# SCH_New-Project_2024-12-08_14-09-2234_20.net
KiCad netlist of a schematic drawn in EasyEDA
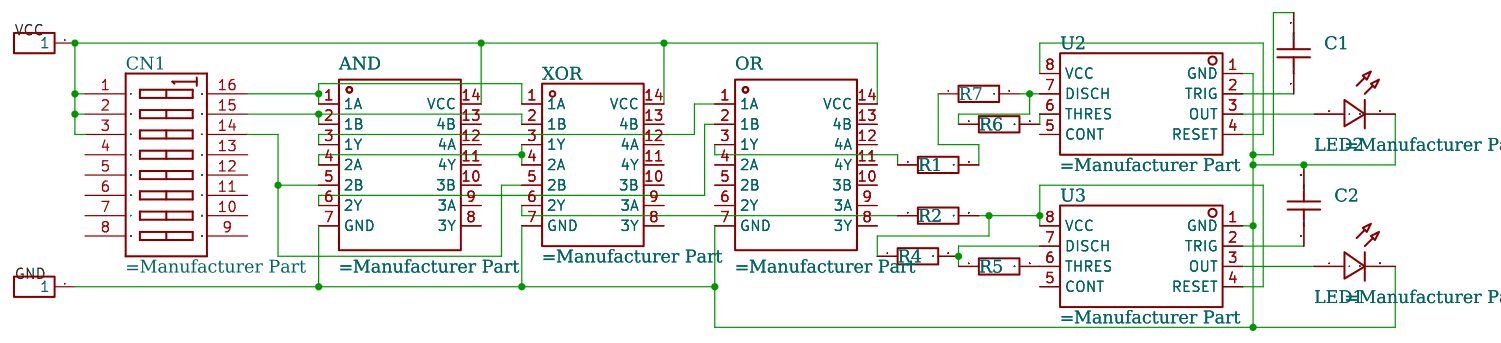
[diagram p0: schematic sheet]

(export (version "E")
  (design (tool "Eeschema 10.0.6"))
  (components
    (comp (ref "AND")
      (value "=Manufacturer Part")
      (fields (field (name "Manufacturer Part") "SN74HC08N") (field (name "Manufacturer") "TI(德州仪器)"))
      (libsource (lib "") (part "Unknown_440_-670"))
    )
    (comp (ref "C1")
      (value "100uF")
      (fields
        (field (name "Manufacturer Part") "50YXJ100MT78X11.5")
        (field (name "Manufacturer") "rubycon(红宝石)")
      )
      (libsource (lib "") (part "Unknown_880_-725"))
    )
    (comp (ref "C2")
      (value "100uF")
      (fields
        (field (name "Manufacturer Part") "50YXJ100MT78X11.5")
        (field (name "Manufacturer") "rubycon(红宝石)")
      )
      (libsource (lib "") (part "Unknown_885_-650"))
    )
    (comp (ref "CN1")
      (value "=Manufacturer Part")
      (fields (field (name "Manufacturer Part") "DS-08RP") (field (name "Manufacturer") "韩国韩荣"))
      (libsource (lib "") (part "Unknown_325_-665"))
    )
    (comp (ref "H1")
      (value "=Manufacturer Part")
      (fields (field (name "Manufacturer Part") "2059-301/998-403") (field (name "Manufacturer") "WAGO(万可)"))
      (libsource (lib "") (part "Unknown_260_-610"))
    )
    (comp (ref "H2")
      (value "=Manufacturer Part")
      (fields (field (name "Manufacturer Part") "2059-301/998-403") (field (name "Manufacturer") "WAGO(万可)"))
      (libsource (lib "") (part "Unknown_260_-730"))
    )
    (comp (ref "LED1")
      (value "=Manufacturer Part")
      (fields (field (name "Manufacturer Part") "LTL-4231N") (field (name "Manufacturer") "LITEON(光宝)"))
      (libsource (lib "") (part "Unknown_910_-620"))
    )
    (comp (ref "LED2")
      (value "=Manufacturer Part")
      (fields (field (name "Manufacturer Part") "LTL-4231N") (field (name "Manufacturer") "LITEON(光宝)"))
      (libsource (lib "") (part "Unknown_910_-695"))
    )
    (comp (ref "OR")
      (value "=Manufacturer Part")
      (fields (field (name "Manufacturer Part") "SN74HC32N") (field (name "Manufacturer") "TI(德州仪器)"))
      (libsource (lib "") (part "Unknown_635_-670"))
    )
    (comp (ref "R1")
      (value "1kΩ")
      (fields (field (name "Manufacturer Part") "RC0402JR-071KL") (field (name "Manufacturer") "YAGEO(国巨)"))
      (libsource (lib "") (part "Unknown_705_-670"))
    )
    (comp (ref "R2")
      (value "1kΩ")
      (fields (field (name "Manufacturer Part") "RC0402JR-071KL") (field (name "Manufacturer") "YAGEO(国巨)"))
      (libsource (lib "") (part "Unknown_705_-645"))
    )
    (comp (ref "R4")
      (value "1kΩ")
      (fields (field (name "Manufacturer Part") "RC0402JR-071KL") (field (name "Manufacturer") "YAGEO(国巨)"))
      (libsource (lib "") (part "Unknown_695_-625"))
    )
    (comp (ref "R5")
      (value "1kΩ")
      (fields (field (name "Manufacturer Part") "RC0402JR-071KL") (field (name "Manufacturer") "YAGEO(国巨)"))
      (libsource (lib "") (part "Unknown_735_-620"))
    )
    (comp (ref "R6")
      (value "1kΩ")
      (fields (field (name "Manufacturer Part") "RC0402JR-071KL") (field (name "Manufacturer") "YAGEO(国巨)"))
      (libsource (lib "") (part "Unknown_735_-690"))
    )
    (comp (ref "R7")
      (value "1kΩ")
      (fields (field (name "Manufacturer Part") "RC0402JR-071KL") (field (name "Manufacturer") "YAGEO(国巨)"))
      (libsource (lib "") (part "Unknown_725_-705"))
    )
    (comp (ref "U2")
      (value "=Manufacturer Part")
      (fields (field (name "Manufacturer Part") "LM555N") (field (name "Manufacturer") "HGSEMI(华冠)"))
      (libsource (lib "") (part "Unknown_805_-700"))
    )
    (comp (ref "U3")
      (value "=Manufacturer Part")
      (fields (field (name "Manufacturer Part") "LM555N") (field (name "Manufacturer") "HGSEMI(华冠)"))
      (libsource (lib "") (part "Unknown_805_-625"))
    )
    (comp (ref "XOR")
      (value "=Manufacturer Part")
      (fields (field (name "Manufacturer Part") "SN74HC86N") (field (name "Manufacturer") "TI(德州仪器)"))
      (libsource (lib "") (part "Unknown_535_-670"))
    )
  )
  (nets
    (net (code "3") (name "Net-(AND-1A)") (class "Default")
      (node (ref "AND") (pin "1") (pinfunction "1A_1") (pintype "unspecified"))
      (node (ref "CN1") (pin "16") (pinfunction "16_16") (pintype "unspecified"))
      (node (ref "XOR") (pin "1") (pinfunction "1A_1") (pintype "unspecified"))
    )
    (net (code "4") (name "Net-(AND-1B)") (class "Default")
      (node (ref "AND") (pin "2") (pinfunction "1B_2") (pintype "unspecified"))
      (node (ref "CN1") (pin "15") (pinfunction "15_15") (pintype "unspecified"))
      (node (ref "XOR") (pin "2") (pinfunction "1B_2") (pintype "unspecified"))
    )
    (net (code "5") (name "Net-(AND-1Y)") (class "Default")
      (node (ref "AND") (pin "3") (pinfunction "1Y_3") (pintype "unspecified"))
      (node (ref "OR") (pin "1") (pinfunction "1A_1") (pintype "unspecified"))
    )
    (net (code "6") (name "Net-(AND-2A)") (class "Default")
      (node (ref "AND") (pin "4") (pinfunction "2A_4") (pintype "unspecified"))
      (node (ref "XOR") (pin "3") (pinfunction "1Y_3") (pintype "unspecified"))
      (node (ref "XOR") (pin "4") (pinfunction "2A_4") (pintype "unspecified"))
    )
    (net (code "7") (name "Net-(AND-2B)") (class "Default")
      (node (ref "AND") (pin "5") (pinfunction "2B_5") (pintype "unspecified"))
      (node (ref "CN1") (pin "14") (pinfunction "14_14") (pintype "unspecified"))
      (node (ref "XOR") (pin "5") (pinfunction "2B_5") (pintype "unspecified"))
    )
    (net (code "8") (name "Net-(AND-2Y)") (class "Default")
      (node (ref "AND") (pin "6") (pinfunction "2Y_6") (pintype "unspecified"))
      (node (ref "OR") (pin "2") (pinfunction "1B_2") (pintype "unspecified"))
    )
    (net (code "9") (name "Net-(AND-GND)") (class "Default")
      (node (ref "AND") (pin "7") (pinfunction "GND_7") (pintype "unspecified"))
      (node (ref "C1") (pin "2") (pinfunction "2_2") (pintype "unspecified"))
      (node (ref "C2") (pin "2") (pinfunction "2_2") (pintype "unspecified"))
      (node (ref "H1") (pin "1") (pinfunction "1_1") (pintype "unspecified"))
      (node (ref "LED1") (pin "2") (pinfunction "C_2") (pintype "unspecified"))
      (node (ref "LED2") (pin "2") (pinfunction "C_2") (pintype "unspecified"))
      (node (ref "OR") (pin "7") (pinfunction "GND_7") (pintype "unspecified"))
      (node (ref "U2") (pin "1") (pinfunction "GND_1") (pintype "unspecified"))
      (node (ref "U3") (pin "1") (pinfunction "GND_1") (pintype "unspecified"))
      (node (ref "XOR") (pin "7") (pinfunction "GND_7") (pintype "unspecified"))
    )
    (net (code "10") (name "Net-(AND-VCC)") (class "Default")
      (node (ref "AND") (pin "14") (pinfunction "VCC_14") (pintype "unspecified"))
      (node (ref "CN1") (pin "1") (pinfunction "A1_1") (pintype "unspecified"))
      (node (ref "CN1") (pin "2") (pinfunction "A2_2") (pintype "unspecified"))
      (node (ref "CN1") (pin "3") (pinfunction "A3_3") (pintype "unspecified"))
      (node (ref "H2") (pin "1") (pinfunction "1_1") (pintype "unspecified"))
      (node (ref "OR") (pin "14") (pinfunction "VCC_14") (pintype "unspecified"))
      (node (ref "XOR") (pin "14") (pinfunction "VCC_14") (pintype "unspecified"))
    )
    (net (code "11") (name "Net-(LED1-A)") (class "Default")
      (node (ref "LED1") (pin "1") (pinfunction "A_1") (pintype "unspecified"))
      (node (ref "U3") (pin "3") (pinfunction "OUT_3") (pintype "unspecified"))
    )
    (net (code "12") (name "Net-(LED2-A)") (class "Default")
      (node (ref "LED2") (pin "1") (pinfunction "A_1") (pintype "unspecified"))
      (node (ref "U2") (pin "3") (pinfunction "OUT_3") (pintype "unspecified"))
    )
    (net (code "13") (name "Net-(OR-1Y)") (class "Default")
      (node (ref "OR") (pin "3") (pinfunction "1Y_3") (pintype "unspecified"))
      (node (ref "R1") (pin "1") (pinfunction "1_1") (pintype "unspecified"))
    )
    (net (code "14") (name "Net-(R1-Pad2)") (class "Default")
      (node (ref "R1") (pin "2") (pinfunction "2_2") (pintype "unspecified"))
      (node (ref "R7") (pin "1") (pinfunction "1_1") (pintype "unspecified"))
    )
    (net (code "15") (name "Net-(U2-DISCH)") (class "Default")
      (node (ref "R6") (pin "1") (pinfunction "1_1") (pintype "unspecified"))
      (node (ref "R7") (pin "2") (pinfunction "2_2") (pintype "unspecified"))
      (node (ref "U2") (pin "7") (pinfunction "DISCH_7") (pintype "unspecified"))
    )
    (net (code "16") (name "Net-(U2-RESET)") (class "Default")
      (node (ref "U2") (pin "4") (pinfunction "RESET_4") (pintype "unspecified"))
      (node (ref "U2") (pin "8") (pinfunction "VCC_8") (pintype "unspecified"))
    )
    (net (code "17") (name "Net-(U2-THRES)") (class "Default")
      (node (ref "R6") (pin "2") (pinfunction "2_2") (pintype "unspecified"))
      (node (ref "U2") (pin "6") (pinfunction "THRES_6") (pintype "unspecified"))
    )
    (net (code "18") (name "Net-(U2-TRIG)") (class "Default")
      (node (ref "C1") (pin "1") (pinfunction "1_1") (pintype "unspecified"))
      (node (ref "U2") (pin "2") (pinfunction "TRIG_2") (pintype "unspecified"))
    )
    (net (code "19") (name "Net-(U3-DISCH)") (class "Default")
      (node (ref "R4") (pin "2") (pinfunction "2_2") (pintype "unspecified"))
      (node (ref "R5") (pin "1") (pinfunction "1_1") (pintype "unspecified"))
      (node (ref "U3") (pin "7") (pinfunction "DISCH_7") (pintype "unspecified"))
    )
    (net (code "20") (name "Net-(U3-RESET)") (class "Default")
      (node (ref "R2") (pin "2") (pinfunction "2_2") (pintype "unspecified"))
      (node (ref "R4") (pin "1") (pinfunction "1_1") (pintype "unspecified"))
      (node (ref "U3") (pin "4") (pinfunction "RESET_4") (pintype "unspecified"))
      (node (ref "U3") (pin "8") (pinfunction "VCC_8") (pintype "unspecified"))
    )
    (net (code "21") (name "Net-(U3-THRES)") (class "Default")
      (node (ref "R5") (pin "2") (pinfunction "2_2") (pintype "unspecified"))
      (node (ref "U3") (pin "6") (pinfunction "THRES_6") (pintype "unspecified"))
    )
    (net (code "22") (name "Net-(U3-TRIG)") (class "Default")
      (node (ref "C2") (pin "1") (pinfunction "1_1") (pintype "unspecified"))
      (node (ref "U3") (pin "2") (pinfunction "TRIG_2") (pintype "unspecified"))
    )
    (net (code "23") (name "Net-(XOR-2Y)") (class "Default")
      (node (ref "R2") (pin "1") (pinfunction "1_1") (pintype "unspecified"))
      (node (ref "XOR") (pin "6") (pinfunction "2Y_6") (pintype "unspecified"))
    )
    (net (code "24") (name "unconnected-(AND-3A-Pad9)") (class "Default")
      (node (ref "AND") (pin "9") (pinfunction "3A_9") (pintype "unspecified"))
    )
    (net (code "25") (name "unconnected-(AND-3B-Pad10)") (class "Default")
      (node (ref "AND") (pin "10") (pinfunction "3B_10") (pintype "unspecified"))
    )
    (net (code "26") (name "unconnected-(AND-3Y-Pad8)") (class "Default")
      (node (ref "AND") (pin "8") (pinfunction "3Y_8") (pintype "unspecified"))
    )
    (net (code "27") (name "unconnected-(AND-4A-Pad12)") (class "Default")
      (node (ref "AND") (pin "12") (pinfunction "4A_12") (pintype "unspecified"))
    )
    (net (code "28") (name "unconnected-(AND-4B-Pad13)") (class "Default")
      (node (ref "AND") (pin "13") (pinfunction "4B_13") (pintype "unspecified"))
    )
    (net (code "29") (name "unconnected-(AND-4Y-Pad11)") (class "Default")
      (node (ref "AND") (pin "11") (pinfunction "4Y_11") (pintype "unspecified"))
    )
    (net (code "30") (name "unconnected-(CN1-A4-Pad4)") (class "Default")
      (node (ref "CN1") (pin "4") (pinfunction "A4_4") (pintype "unspecified"))
    )
    (net (code "31") (name "unconnected-(CN1-A5-Pad5)") (class "Default")
      (node (ref "CN1") (pin "5") (pinfunction "A5_5") (pintype "unspecified"))
    )
    (net (code "32") (name "unconnected-(CN1-A6-Pad6)") (class "Default")
      (node (ref "CN1") (pin "6") (pinfunction "A6_6") (pintype "unspecified"))
    )
    (net (code "33") (name "unconnected-(CN1-A7-Pad7)") (class "Default")
      (node (ref "CN1") (pin "7") (pinfunction "A7_7") (pintype "unspecified"))
    )
    (net (code "34") (name "unconnected-(CN1-A8-Pad8)") (class "Default")
      (node (ref "CN1") (pin "8") (pinfunction "A8_8") (pintype "unspecified"))
    )
    (net (code "35") (name "unconnected-(CN1-Pad9)") (class "Default")
      (node (ref "CN1") (pin "9") (pinfunction "9_9") (pintype "unspecified"))
    )
    (net (code "36") (name "unconnected-(CN1-Pad10)") (class "Default")
      (node (ref "CN1") (pin "10") (pinfunction "10_10") (pintype "unspecified"))
    )
    (net (code "37") (name "unconnected-(CN1-Pad11)") (class "Default")
      (node (ref "CN1") (pin "11") (pinfunction "11_11") (pintype "unspecified"))
    )
    (net (code "38") (name "unconnected-(CN1-Pad12)") (class "Default")
      (node (ref "CN1") (pin "12") (pinfunction "12_12") (pintype "unspecified"))
    )
    (net (code "39") (name "unconnected-(CN1-Pad13)") (class "Default")
      (node (ref "CN1") (pin "13") (pinfunction "13_13") (pintype "unspecified"))
    )
    (net (code "40") (name "unconnected-(OR-2A-Pad4)") (class "Default")
      (node (ref "OR") (pin "4") (pinfunction "2A_4") (pintype "unspecified"))
    )
    (net (code "41") (name "unconnected-(OR-2B-Pad5)") (class "Default")
      (node (ref "OR") (pin "5") (pinfunction "2B_5") (pintype "unspecified"))
    )
    (net (code "42") (name "unconnected-(OR-2Y-Pad6)") (class "Default")
      (node (ref "OR") (pin "6") (pinfunction "2Y_6") (pintype "unspecified"))
    )
    (net (code "43") (name "unconnected-(OR-3A-Pad9)") (class "Default")
      (node (ref "OR") (pin "9") (pinfunction "3A_9") (pintype "unspecified"))
    )
    (net (code "44") (name "unconnected-(OR-3B-Pad10)") (class "Default")
      (node (ref "OR") (pin "10") (pinfunction "3B_10") (pintype "unspecified"))
    )
    (net (code "45") (name "unconnected-(OR-3Y-Pad8)") (class "Default")
      (node (ref "OR") (pin "8") (pinfunction "3Y_8") (pintype "unspecified"))
    )
    (net (code "46") (name "unconnected-(OR-4A-Pad12)") (class "Default")
      (node (ref "OR") (pin "12") (pinfunction "4A_12") (pintype "unspecified"))
    )
    (net (code "47") (name "unconnected-(OR-4B-Pad13)") (class "Default")
      (node (ref "OR") (pin "13") (pinfunction "4B_13") (pintype "unspecified"))
    )
    (net (code "48") (name "unconnected-(OR-4Y-Pad11)") (class "Default")
      (node (ref "OR") (pin "11") (pinfunction "4Y_11") (pintype "unspecified"))
    )
    (net (code "49") (name "unconnected-(U2-CONT-Pad5)") (class "Default")
      (node (ref "U2") (pin "5") (pinfunction "CONT_5") (pintype "unspecified"))
    )
    (net (code "50") (name "unconnected-(U3-CONT-Pad5)") (class "Default")
      (node (ref "U3") (pin "5") (pinfunction "CONT_5") (pintype "unspecified"))
    )
    (net (code "51") (name "unconnected-(XOR-3A-Pad9)") (class "Default")
      (node (ref "XOR") (pin "9") (pinfunction "3A_9") (pintype "unspecified"))
    )
    (net (code "52") (name "unconnected-(XOR-3B-Pad10)") (class "Default")
      (node (ref "XOR") (pin "10") (pinfunction "3B_10") (pintype "unspecified"))
    )
    (net (code "53") (name "unconnected-(XOR-3Y-Pad8)") (class "Default")
      (node (ref "XOR") (pin "8") (pinfunction "3Y_8") (pintype "unspecified"))
    )
    (net (code "54") (name "unconnected-(XOR-4A-Pad12)") (class "Default")
      (node (ref "XOR") (pin "12") (pinfunction "4A_12") (pintype "unspecified"))
    )
    (net (code "55") (name "unconnected-(XOR-4B-Pad13)") (class "Default")
      (node (ref "XOR") (pin "13") (pinfunction "4B_13") (pintype "unspecified"))
    )
    (net (code "56") (name "unconnected-(XOR-4Y-Pad11)") (class "Default")
      (node (ref "XOR") (pin "11") (pinfunction "4Y_11") (pintype "unspecified"))
    )
  )
)
